# Spindle_Sync.net
KiCad netlist of a schematic drawn in Altium Designer
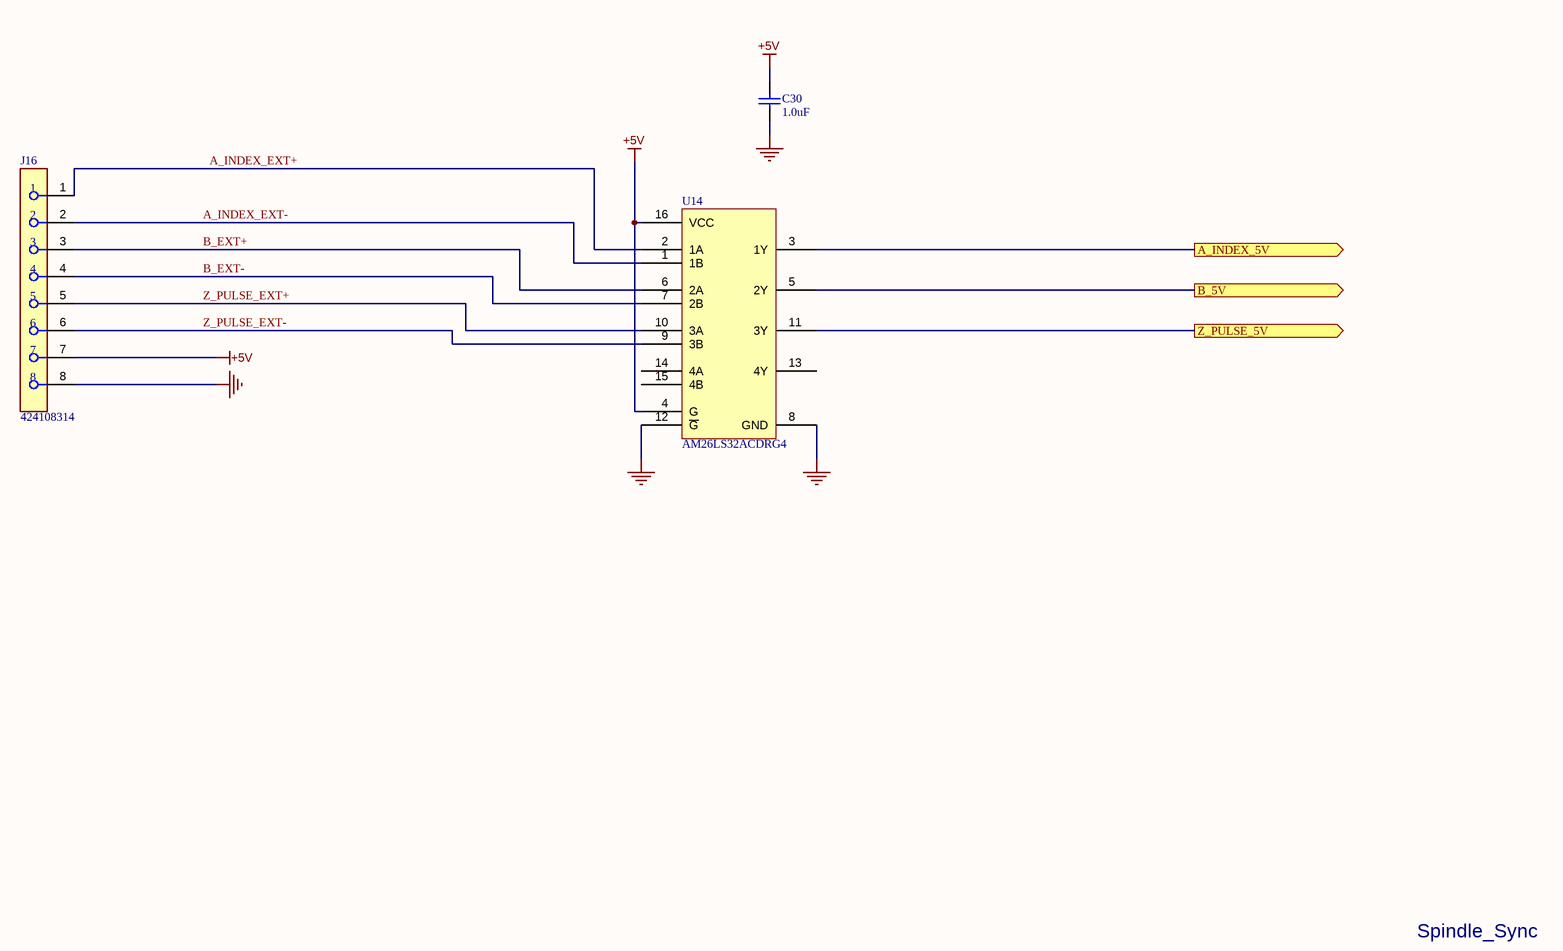
[diagram p0: Spindle_Sync.SchDoc]

(export (version "E")
  (design (tool "Eeschema 10.0.6"))
  (components
    (comp (ref "C30")
      (value "1.0uF")
      (footprint "0402_C")
      (description "Chip capacitor")
      (fields
        (field (name "MANUFACTURER") "Samsung Electro-Mechanics")
        (field (name "PARTNUMBER") "CL05A105KA5NQNC")
      )
      (libsource (lib "Cap") (part "0402 1.0uF (105) 10% 25V"))
    )
    (comp (ref "J16")
      (value "424108314")
      (footprint "FP-5555799-1-MFG")
      (description "CONN MOD JACK 8P8C VERT UNSHLD")
      (libsource (lib "PrintNC_GRBLHAL_Breakout") (part "a32a9c29f5c2290c50060dfb8ad7212"))
    )
    (comp (ref "U14")
      (value "AM26LS32ACDRG4")
      (footprint "SOIC-16_150mil")
      (description "接口芯片")
      (libsource (lib "PrintNC_GRBLHAL_Breakout") (part "AM26LS32ACDRG4_[C6180]"))
    )
  )
  (nets
    (net (code "1") (name "+5V") (class "Default")
      (node (ref "C30") (pin "2") (pinfunction "2_2") (pintype "passive"))
      (node (ref "J16") (pin "7") (pinfunction "7_7") (pintype "passive"))
      (node (ref "U14") (pin "16") (pinfunction "VCC_16") (pintype "passive"))
      (node (ref "U14") (pin "4") (pinfunction "G_4") (pintype "passive"))
    )
    (net (code "2") (name "/A_INDEX_5V") (class "Default")
      (node (ref "U14") (pin "3") (pinfunction "1Y_3") (pintype "passive"))
    )
    (net (code "3") (name "/A_INDEX_EXT+") (class "Default")
      (node (ref "J16") (pin "1") (pinfunction "1_1") (pintype "passive"))
      (node (ref "U14") (pin "2") (pinfunction "1A_2") (pintype "passive"))
    )
    (net (code "4") (name "/A_INDEX_EXT-") (class "Default")
      (node (ref "J16") (pin "2") (pinfunction "2_2") (pintype "passive"))
      (node (ref "U14") (pin "1") (pinfunction "1B_1") (pintype "passive"))
    )
    (net (code "5") (name "/B_5V") (class "Default")
      (node (ref "U14") (pin "5") (pinfunction "2Y_5") (pintype "passive"))
    )
    (net (code "6") (name "/B_EXT+") (class "Default")
      (node (ref "J16") (pin "3") (pinfunction "3_3") (pintype "passive"))
      (node (ref "U14") (pin "6") (pinfunction "2A_6") (pintype "passive"))
    )
    (net (code "7") (name "/B_EXT-") (class "Default")
      (node (ref "J16") (pin "4") (pinfunction "4_4") (pintype "passive"))
      (node (ref "U14") (pin "7") (pinfunction "2B_7") (pintype "passive"))
    )
    (net (code "8") (name "/Z_PULSE_5V") (class "Default")
      (node (ref "U14") (pin "11") (pinfunction "3Y_11") (pintype "passive"))
    )
    (net (code "9") (name "/Z_PULSE_EXT+") (class "Default")
      (node (ref "J16") (pin "5") (pinfunction "5_5") (pintype "passive"))
      (node (ref "U14") (pin "10") (pinfunction "3A_10") (pintype "passive"))
    )
    (net (code "10") (name "/Z_PULSE_EXT-") (class "Default")
      (node (ref "J16") (pin "6") (pinfunction "6_6") (pintype "passive"))
      (node (ref "U14") (pin "9") (pinfunction "3B_9") (pintype "passive"))
    )
    (net (code "11") (name "GND") (class "Default")
      (node (ref "C30") (pin "1") (pinfunction "1_1") (pintype "passive"))
      (node (ref "J16") (pin "8") (pinfunction "8_8") (pintype "passive"))
      (node (ref "U14") (pin "12") (pinfunction "~{G}_12") (pintype "passive"))
      (node (ref "U14") (pin "8") (pinfunction "GND_8") (pintype "passive"))
    )
    (net (code "12") (name "unconnected-(U14-4A-Pad14)") (class "Default")
      (node (ref "U14") (pin "14") (pinfunction "4A_14") (pintype "passive"))
    )
    (net (code "13") (name "unconnected-(U14-4B-Pad15)") (class "Default")
      (node (ref "U14") (pin "15") (pinfunction "4B_15") (pintype "passive"))
    )
    (net (code "14") (name "unconnected-(U14-4Y-Pad13)") (class "Default")
      (node (ref "U14") (pin "13") (pinfunction "4Y_13") (pintype "passive"))
    )
  )
)
